# LF_SFF_AC_DC.net
KiCad netlist of a schematic drawn in Altium Designer
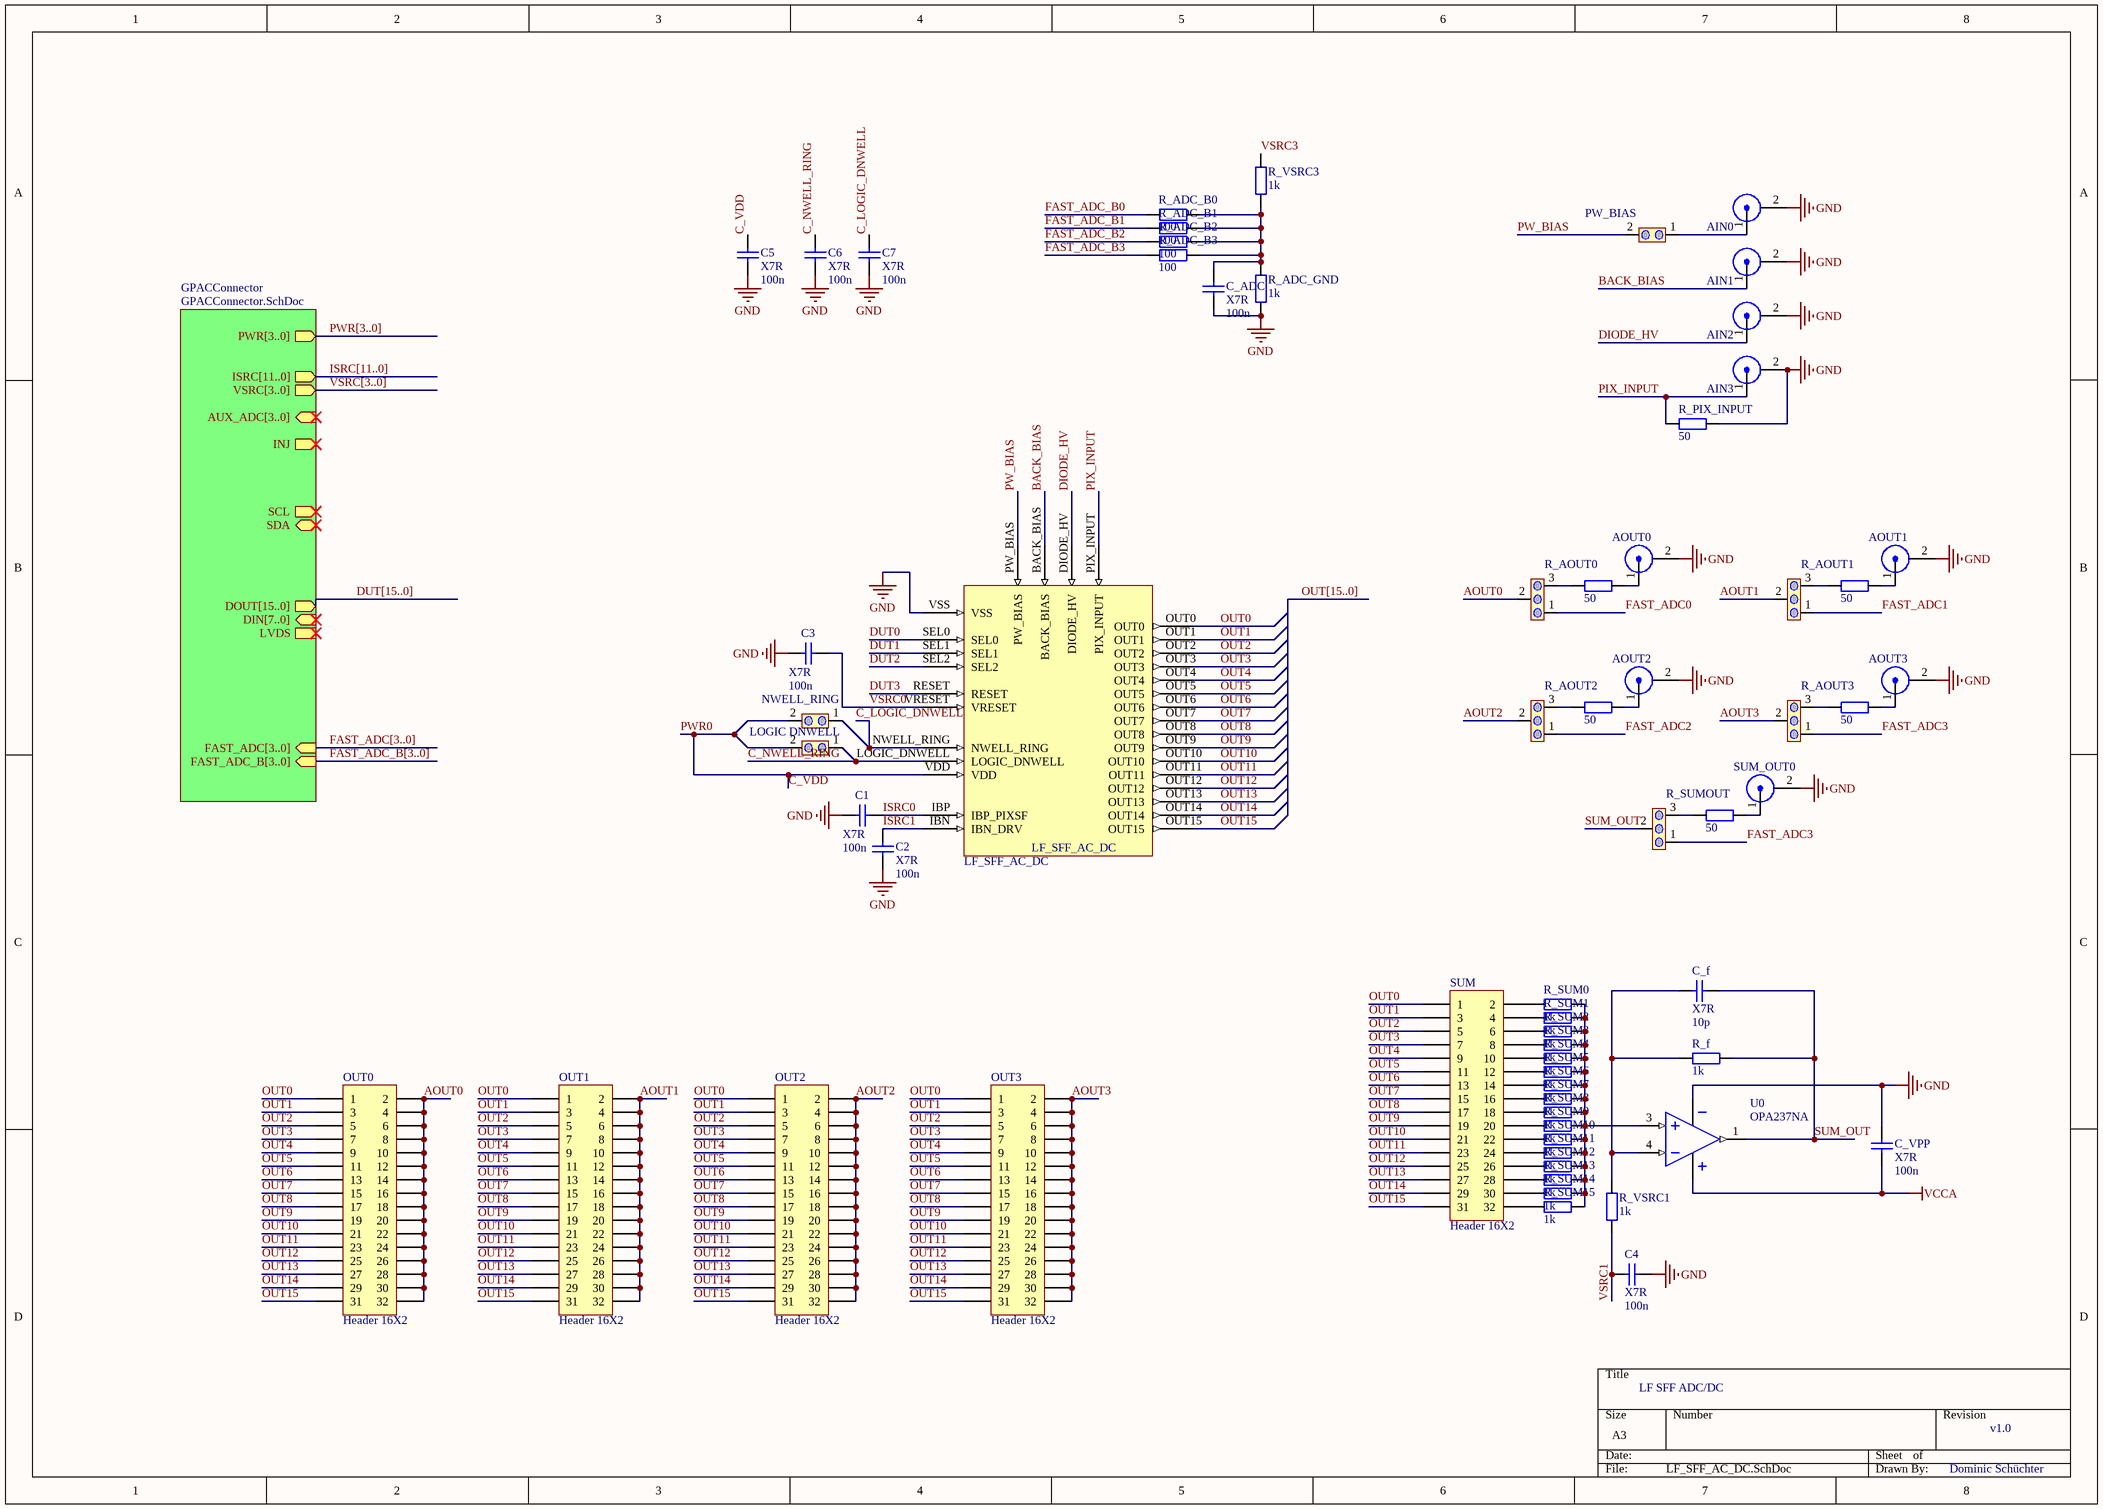
[diagram p0: LF_SFF_AC_DC.SchDoc]

(export (version "E")
  (design (tool "Eeschema 10.0.6"))
  (components
    (comp (ref "AIN0")
      (value "-")
      (footprint "LEMO horiz.")
      (description "LEMO/BNC Buchse, aufrecht od. gewinkelt")
      (fields (field (name "PUBLISHER") "Silab C.H."))
      (libsource (lib "Silab_Lib") (part "LEMO coax"))
    )
    (comp (ref "AIN1")
      (value "-")
      (footprint "LEMO horiz.")
      (description "LEMO/BNC Buchse, aufrecht od. gewinkelt")
      (fields (field (name "PUBLISHER") "Silab C.H."))
      (libsource (lib "Silab_Lib") (part "LEMO coax"))
    )
    (comp (ref "AIN2")
      (value "-")
      (footprint "LEMO horiz.")
      (description "LEMO/BNC Buchse, aufrecht od. gewinkelt")
      (fields (field (name "PUBLISHER") "Silab C.H."))
      (libsource (lib "Silab_Lib") (part "LEMO coax"))
    )
    (comp (ref "AIN3")
      (value "-")
      (footprint "LEMO horiz.")
      (description "LEMO/BNC Buchse, aufrecht od. gewinkelt")
      (fields (field (name "PUBLISHER") "Silab C.H."))
      (libsource (lib "Silab_Lib") (part "LEMO coax"))
    )
    (comp (ref "AOUT0")
      (value "-")
      (footprint "LEMO horiz.")
      (description "LEMO/BNC Buchse, aufrecht od. gewinkelt")
      (fields (field (name "PUBLISHER") "Silab C.H."))
      (libsource (lib "Silab_Lib") (part "LEMO coax"))
    )
    (comp (ref "AOUT1")
      (value "-")
      (footprint "LEMO horiz.")
      (description "LEMO/BNC Buchse, aufrecht od. gewinkelt")
      (fields (field (name "PUBLISHER") "Silab C.H."))
      (libsource (lib "Silab_Lib") (part "LEMO coax"))
    )
    (comp (ref "AOUT2")
      (value "-")
      (footprint "LEMO horiz.")
      (description "LEMO/BNC Buchse, aufrecht od. gewinkelt")
      (fields (field (name "PUBLISHER") "Silab C.H."))
      (libsource (lib "Silab_Lib") (part "LEMO coax"))
    )
    (comp (ref "AOUT3")
      (value "-")
      (footprint "LEMO horiz.")
      (description "LEMO/BNC Buchse, aufrecht od. gewinkelt")
      (fields (field (name "PUBLISHER") "Silab C.H."))
      (libsource (lib "Silab_Lib") (part "LEMO coax"))
    )
    (comp (ref "AOUT_SEL0")
      (value "-")
      (footprint "HDR 1x3")
      (description "Jumper, Solderbridge 1x3")
      (fields (field (name "PUBLISHER") "Silab C.H."))
      (libsource (lib "Silab_Lib") (part "JUMPER 1X3S"))
    )
    (comp (ref "AOUT_SEL1")
      (value "-")
      (footprint "HDR 1x3")
      (description "Jumper, Solderbridge 1x3")
      (fields (field (name "PUBLISHER") "Silab C.H."))
      (libsource (lib "Silab_Lib") (part "JUMPER 1X3S"))
    )
    (comp (ref "AOUT_SEL2")
      (value "-")
      (footprint "HDR 1x3")
      (description "Jumper, Solderbridge 1x3")
      (fields (field (name "PUBLISHER") "Silab C.H."))
      (libsource (lib "Silab_Lib") (part "JUMPER 1X3S"))
    )
    (comp (ref "AOUT_SEL3")
      (value "-")
      (footprint "HDR 1x3")
      (description "Jumper, Solderbridge 1x3")
      (fields (field (name "PUBLISHER") "Silab C.H."))
      (libsource (lib "Silab_Lib") (part "JUMPER 1X3S"))
    )
    (comp (ref "C1")
      (value "X7R")
      (footprint "C0603_imp_N")
      (description "Capacitor")
      (fields (field (name "ALTIUM_VALUE") "100n") (field (name "PUBLISHER") "Silab J.S."))
      (libsource (lib "Silab_Lib") (part "C"))
    )
    (comp (ref "C2")
      (value "X7R")
      (footprint "C0603_imp_N")
      (description "Capacitor")
      (fields (field (name "ALTIUM_VALUE") "100n") (field (name "PUBLISHER") "Silab J.S."))
      (libsource (lib "Silab_Lib") (part "C"))
    )
    (comp (ref "C3")
      (value "X7R")
      (footprint "C0603_imp_N")
      (description "Capacitor")
      (fields (field (name "ALTIUM_VALUE") "100n") (field (name "PUBLISHER") "Silab J.S."))
      (libsource (lib "Silab_Lib") (part "C"))
    )
    (comp (ref "C4")
      (value "X7R")
      (footprint "C0603_imp_N")
      (description "Capacitor")
      (fields (field (name "ALTIUM_VALUE") "100n") (field (name "PUBLISHER") "Silab J.S."))
      (libsource (lib "Silab_Lib") (part "C"))
    )
    (comp (ref "C5")
      (value "X7R")
      (footprint "C0603_imp_N")
      (description "Capacitor")
      (fields (field (name "ALTIUM_VALUE") "100n") (field (name "PUBLISHER") "Silab J.S."))
      (libsource (lib "Silab_Lib") (part "C"))
    )
    (comp (ref "C6")
      (value "X7R")
      (footprint "C0603_imp_N")
      (description "Capacitor")
      (fields (field (name "ALTIUM_VALUE") "100n") (field (name "PUBLISHER") "Silab J.S."))
      (libsource (lib "Silab_Lib") (part "C"))
    )
    (comp (ref "C7")
      (value "X7R")
      (footprint "C0603_imp_N")
      (description "Capacitor")
      (fields (field (name "ALTIUM_VALUE") "100n") (field (name "PUBLISHER") "Silab J.S."))
      (libsource (lib "Silab_Lib") (part "C"))
    )
    (comp (ref "C_ADC")
      (value "X7R")
      (footprint "C0603_imp_N")
      (description "Capacitor")
      (fields (field (name "ALTIUM_VALUE") "100n") (field (name "PUBLISHER") "Silab J.S."))
      (libsource (lib "Silab_Lib") (part "C"))
    )
    (comp (ref "C_f")
      (value "X7R")
      (footprint "C0603_imp_N")
      (description "Capacitor")
      (fields (field (name "ALTIUM_VALUE") "10p") (field (name "PUBLISHER") "Silab J.S."))
      (libsource (lib "Silab_Lib") (part "C"))
    )
    (comp (ref "C_VPP")
      (value "X7R")
      (footprint "C0603_imp_N")
      (description "Capacitor")
      (fields (field (name "ALTIUM_VALUE") "100n") (field (name "PUBLISHER") "Silab J.S."))
      (libsource (lib "Silab_Lib") (part "C"))
    )
    (comp (ref "LF_SFF_AC_DC")
      (value "LF_SFF_AC_DC")
      (footprint "LF_SFF_COMBI")
      (libsource (lib "LF_SFF_AC") (part "LF_SFF_AC"))
    )
    (comp (ref "LOGIC DNWELL")
      (value "-")
      (footprint "CON 1x2 std")
      (description "Jumper, Solderbridge 1x2")
      (fields (field (name "PUBLISHER") "Silab C.H."))
      (libsource (lib "Silab_Lib") (part "JUMPER 1X2S"))
    )
    (comp (ref "NWELL_RING")
      (value "-")
      (footprint "CON 1x2 std")
      (description "Jumper, Solderbridge 1x2")
      (fields (field (name "PUBLISHER") "Silab C.H."))
      (libsource (lib "Silab_Lib") (part "JUMPER 1X2S"))
    )
    (comp (ref "OUT0")
      (value "Header 16X2")
      (footprint "HDR2X16")
      (description "Header, 16-Pin, Dual row")
      (fields (field (name "PUBLISHER") "Altium Limited"))
      (libsource (lib "Miscellaneous Connectors") (part "Header 16X2"))
    )
    (comp (ref "OUT1")
      (value "Header 16X2")
      (footprint "HDR2X16")
      (description "Header, 16-Pin, Dual row")
      (fields (field (name "PUBLISHER") "Altium Limited"))
      (libsource (lib "Miscellaneous Connectors") (part "Header 16X2"))
    )
    (comp (ref "OUT2")
      (value "Header 16X2")
      (footprint "HDR2X16")
      (description "Header, 16-Pin, Dual row")
      (fields (field (name "PUBLISHER") "Altium Limited"))
      (libsource (lib "Miscellaneous Connectors") (part "Header 16X2"))
    )
    (comp (ref "OUT3")
      (value "Header 16X2")
      (footprint "HDR2X16")
      (description "Header, 16-Pin, Dual row")
      (fields (field (name "PUBLISHER") "Altium Limited"))
      (libsource (lib "Miscellaneous Connectors") (part "Header 16X2"))
    )
    (comp (ref "PW_BIAS")
      (value "-")
      (footprint "CON 1x2 std")
      (description "Jumper, Solderbridge 1x2")
      (fields (field (name "PUBLISHER") "Silab C.H."))
      (libsource (lib "Silab_Lib") (part "JUMPER 1X2S"))
    )
    (comp (ref "R_ADC_B0")
      (value "100")
      (footprint "R0603_imp_N")
      (description "SMD Chip Resistor")
      (fields (field (name "Comment") "R") (field (name "PUBLISHER") "Silab J.S."))
      (libsource (lib "Silab_Lib") (part "R"))
    )
    (comp (ref "R_ADC_B1")
      (value "100")
      (footprint "R0603_imp_N")
      (description "SMD Chip Resistor")
      (fields (field (name "Comment") "R") (field (name "PUBLISHER") "Silab J.S."))
      (libsource (lib "Silab_Lib") (part "R"))
    )
    (comp (ref "R_ADC_B2")
      (value "100")
      (footprint "R0603_imp_N")
      (description "SMD Chip Resistor")
      (fields (field (name "Comment") "R") (field (name "PUBLISHER") "Silab J.S."))
      (libsource (lib "Silab_Lib") (part "R"))
    )
    (comp (ref "R_ADC_B3")
      (value "100")
      (footprint "R0603_imp_N")
      (description "SMD Chip Resistor")
      (fields (field (name "Comment") "R") (field (name "PUBLISHER") "Silab J.S."))
      (libsource (lib "Silab_Lib") (part "R"))
    )
    (comp (ref "R_ADC_GND")
      (value "1k")
      (footprint "R0603_imp_N")
      (description "SMD Chip Resistor")
      (fields (field (name "Comment") "R") (field (name "PUBLISHER") "Silab J.S."))
      (libsource (lib "Silab_Lib") (part "R"))
    )
    (comp (ref "R_AOUT0")
      (value "50")
      (footprint "R0603_imp_N")
      (description "SMD Chip Resistor")
      (fields (field (name "Comment") "R") (field (name "PUBLISHER") "Silab J.S."))
      (libsource (lib "Silab_Lib") (part "R"))
    )
    (comp (ref "R_AOUT1")
      (value "50")
      (footprint "R0603_imp_N")
      (description "SMD Chip Resistor")
      (fields (field (name "Comment") "R") (field (name "PUBLISHER") "Silab J.S."))
      (libsource (lib "Silab_Lib") (part "R"))
    )
    (comp (ref "R_AOUT2")
      (value "50")
      (footprint "R0603_imp_N")
      (description "SMD Chip Resistor")
      (fields (field (name "Comment") "R") (field (name "PUBLISHER") "Silab J.S."))
      (libsource (lib "Silab_Lib") (part "R"))
    )
    (comp (ref "R_AOUT3")
      (value "50")
      (footprint "R0603_imp_N")
      (description "SMD Chip Resistor")
      (fields (field (name "Comment") "R") (field (name "PUBLISHER") "Silab J.S."))
      (libsource (lib "Silab_Lib") (part "R"))
    )
    (comp (ref "R_f")
      (value "1k")
      (footprint "R0805_imp_M")
      (description "SMD Chip Resistor")
      (fields (field (name "Comment") "R") (field (name "PUBLISHER") "Silab J.S."))
      (libsource (lib "Silab_Lib") (part "R"))
    )
    (comp (ref "R_PIX_INPUT")
      (value "50")
      (footprint "R0603_imp_N")
      (description "SMD Chip Resistor")
      (fields (field (name "Comment") "R") (field (name "PUBLISHER") "Silab J.S."))
      (libsource (lib "Silab_Lib") (part "R"))
    )
    (comp (ref "R_SUM0")
      (value "1k")
      (footprint "R0805_imp_M")
      (description "SMD Chip Resistor")
      (fields (field (name "Comment") "R") (field (name "PUBLISHER") "Silab J.S."))
      (libsource (lib "Silab_Lib") (part "R"))
    )
    (comp (ref "R_SUM1")
      (value "1k")
      (footprint "R0805_imp_M")
      (description "SMD Chip Resistor")
      (fields (field (name "Comment") "R") (field (name "PUBLISHER") "Silab J.S."))
      (libsource (lib "Silab_Lib") (part "R"))
    )
    (comp (ref "R_SUM2")
      (value "1k")
      (footprint "R0805_imp_M")
      (description "SMD Chip Resistor")
      (fields (field (name "Comment") "R") (field (name "PUBLISHER") "Silab J.S."))
      (libsource (lib "Silab_Lib") (part "R"))
    )
    (comp (ref "R_SUM3")
      (value "1k")
      (footprint "R0805_imp_M")
      (description "SMD Chip Resistor")
      (fields (field (name "Comment") "R") (field (name "PUBLISHER") "Silab J.S."))
      (libsource (lib "Silab_Lib") (part "R"))
    )
    (comp (ref "R_SUM4")
      (value "1k")
      (footprint "R0805_imp_M")
      (description "SMD Chip Resistor")
      (fields (field (name "Comment") "R") (field (name "PUBLISHER") "Silab J.S."))
      (libsource (lib "Silab_Lib") (part "R"))
    )
    (comp (ref "R_SUM5")
      (value "1k")
      (footprint "R0805_imp_M")
      (description "SMD Chip Resistor")
      (fields (field (name "Comment") "R") (field (name "PUBLISHER") "Silab J.S."))
      (libsource (lib "Silab_Lib") (part "R"))
    )
    (comp (ref "R_SUM6")
      (value "1k")
      (footprint "R0805_imp_M")
      (description "SMD Chip Resistor")
      (fields (field (name "Comment") "R") (field (name "PUBLISHER") "Silab J.S."))
      (libsource (lib "Silab_Lib") (part "R"))
    )
    (comp (ref "R_SUM7")
      (value "1k")
      (footprint "R0805_imp_M")
      (description "SMD Chip Resistor")
      (fields (field (name "Comment") "R") (field (name "PUBLISHER") "Silab J.S."))
      (libsource (lib "Silab_Lib") (part "R"))
    )
    (comp (ref "R_SUM8")
      (value "1k")
      (footprint "R0805_imp_M")
      (description "SMD Chip Resistor")
      (fields (field (name "Comment") "R") (field (name "PUBLISHER") "Silab J.S."))
      (libsource (lib "Silab_Lib") (part "R"))
    )
    (comp (ref "R_SUM9")
      (value "1k")
      (footprint "R0805_imp_M")
      (description "SMD Chip Resistor")
      (fields (field (name "Comment") "R") (field (name "PUBLISHER") "Silab J.S."))
      (libsource (lib "Silab_Lib") (part "R"))
    )
    (comp (ref "R_SUM10")
      (value "1k")
      (footprint "R0805_imp_M")
      (description "SMD Chip Resistor")
      (fields (field (name "Comment") "R") (field (name "PUBLISHER") "Silab J.S."))
      (libsource (lib "Silab_Lib") (part "R"))
    )
    (comp (ref "R_SUM11")
      (value "1k")
      (footprint "R0805_imp_M")
      (description "SMD Chip Resistor")
      (fields (field (name "Comment") "R") (field (name "PUBLISHER") "Silab J.S."))
      (libsource (lib "Silab_Lib") (part "R"))
    )
    (comp (ref "R_SUM12")
      (value "1k")
      (footprint "R0805_imp_M")
      (description "SMD Chip Resistor")
      (fields (field (name "Comment") "R") (field (name "PUBLISHER") "Silab J.S."))
      (libsource (lib "Silab_Lib") (part "R"))
    )
    (comp (ref "R_SUM13")
      (value "1k")
      (footprint "R0805_imp_M")
      (description "SMD Chip Resistor")
      (fields (field (name "Comment") "R") (field (name "PUBLISHER") "Silab J.S."))
      (libsource (lib "Silab_Lib") (part "R"))
    )
    (comp (ref "R_SUM14")
      (value "1k")
      (footprint "R0805_imp_M")
      (description "SMD Chip Resistor")
      (fields (field (name "Comment") "R") (field (name "PUBLISHER") "Silab J.S."))
      (libsource (lib "Silab_Lib") (part "R"))
    )
    (comp (ref "R_SUM15")
      (value "1k")
      (footprint "R0805_imp_M")
      (description "SMD Chip Resistor")
      (fields (field (name "Comment") "R") (field (name "PUBLISHER") "Silab J.S."))
      (libsource (lib "Silab_Lib") (part "R"))
    )
    (comp (ref "R_SUMOUT")
      (value "50")
      (footprint "R0603_imp_N")
      (description "SMD Chip Resistor")
      (fields (field (name "Comment") "R") (field (name "PUBLISHER") "Silab J.S."))
      (libsource (lib "Silab_Lib") (part "R"))
    )
    (comp (ref "R_VSRC1")
      (value "1k")
      (footprint "R0805_imp_M")
      (description "SMD Chip Resistor")
      (fields (field (name "Comment") "R") (field (name "PUBLISHER") "Silab J.S."))
      (libsource (lib "Silab_Lib") (part "R"))
    )
    (comp (ref "R_VSRC3")
      (value "1k")
      (footprint "R0603_imp_N")
      (description "SMD Chip Resistor")
      (fields (field (name "Comment") "R") (field (name "PUBLISHER") "Silab J.S."))
      (libsource (lib "Silab_Lib") (part "R"))
    )
    (comp (ref "SUM")
      (value "Header 16X2")
      (footprint "HDR2X16")
      (description "Header, 16-Pin, Dual row")
      (fields (field (name "PUBLISHER") "Altium Limited"))
      (libsource (lib "Miscellaneous Connectors") (part "Header 16X2"))
    )
    (comp (ref "SUM_OUT0")
      (value "-")
      (footprint "LEMO horiz.")
      (description "LEMO/BNC Buchse, aufrecht od. gewinkelt")
      (fields (field (name "PUBLISHER") "Silab C.H."))
      (libsource (lib "Silab_Lib") (part "LEMO coax"))
    )
    (comp (ref "SUM_SELECT")
      (value "-")
      (footprint "HDR 1x3")
      (description "Jumper, Solderbridge 1x3")
      (fields (field (name "PUBLISHER") "Silab C.H."))
      (libsource (lib "Silab_Lib") (part "JUMPER 1X3S"))
    )
    (comp (ref "U0")
      (value "OPA237")
      (footprint "SOT23-5")
      (description "OpAmp (TI), single supply up to +36V;")
      (fields (field (name "TYPE_1") "OPA237NA") (field (name "PUBLISHER") "Silab J.S."))
      (libsource (lib "Silab_Lib") (part "OPA237"))
    )
  )
  (nets
    (net (code "27") (name "/AOUT0") (class "Default")
      (node (ref "AOUT_SEL0") (pin "2") (pinfunction "2_2") (pintype "passive"))
      (node (ref "OUT0") (pin "10") (pinfunction "10_10") (pintype "passive"))
      (node (ref "OUT0") (pin "12") (pinfunction "12_12") (pintype "passive"))
      (node (ref "OUT0") (pin "14") (pinfunction "14_14") (pintype "passive"))
      (node (ref "OUT0") (pin "16") (pinfunction "16_16") (pintype "passive"))
      (node (ref "OUT0") (pin "18") (pinfunction "18_18") (pintype "passive"))
      (node (ref "OUT0") (pin "2") (pinfunction "2_2") (pintype "passive"))
      (node (ref "OUT0") (pin "20") (pinfunction "20_20") (pintype "passive"))
      (node (ref "OUT0") (pin "22") (pinfunction "22_22") (pintype "passive"))
      (node (ref "OUT0") (pin "24") (pinfunction "24_24") (pintype "passive"))
      (node (ref "OUT0") (pin "26") (pinfunction "26_26") (pintype "passive"))
      (node (ref "OUT0") (pin "28") (pinfunction "28_28") (pintype "passive"))
      (node (ref "OUT0") (pin "30") (pinfunction "30_30") (pintype "passive"))
      (node (ref "OUT0") (pin "32") (pinfunction "32_32") (pintype "passive"))
      (node (ref "OUT0") (pin "4") (pinfunction "4_4") (pintype "passive"))
      (node (ref "OUT0") (pin "6") (pinfunction "6_6") (pintype "passive"))
      (node (ref "OUT0") (pin "8") (pinfunction "8_8") (pintype "passive"))
    )
    (net (code "28") (name "/AOUT1") (class "Default")
      (node (ref "AOUT_SEL1") (pin "2") (pinfunction "2_2") (pintype "passive"))
      (node (ref "OUT1") (pin "10") (pinfunction "10_10") (pintype "passive"))
      (node (ref "OUT1") (pin "12") (pinfunction "12_12") (pintype "passive"))
      (node (ref "OUT1") (pin "14") (pinfunction "14_14") (pintype "passive"))
      (node (ref "OUT1") (pin "16") (pinfunction "16_16") (pintype "passive"))
      (node (ref "OUT1") (pin "18") (pinfunction "18_18") (pintype "passive"))
      (node (ref "OUT1") (pin "2") (pinfunction "2_2") (pintype "passive"))
      (node (ref "OUT1") (pin "20") (pinfunction "20_20") (pintype "passive"))
      (node (ref "OUT1") (pin "22") (pinfunction "22_22") (pintype "passive"))
      (node (ref "OUT1") (pin "24") (pinfunction "24_24") (pintype "passive"))
      (node (ref "OUT1") (pin "26") (pinfunction "26_26") (pintype "passive"))
      (node (ref "OUT1") (pin "28") (pinfunction "28_28") (pintype "passive"))
      (node (ref "OUT1") (pin "30") (pinfunction "30_30") (pintype "passive"))
      (node (ref "OUT1") (pin "32") (pinfunction "32_32") (pintype "passive"))
      (node (ref "OUT1") (pin "4") (pinfunction "4_4") (pintype "passive"))
      (node (ref "OUT1") (pin "6") (pinfunction "6_6") (pintype "passive"))
      (node (ref "OUT1") (pin "8") (pinfunction "8_8") (pintype "passive"))
    )
    (net (code "29") (name "/AOUT2") (class "Default")
      (node (ref "AOUT_SEL2") (pin "2") (pinfunction "2_2") (pintype "passive"))
      (node (ref "OUT2") (pin "10") (pinfunction "10_10") (pintype "passive"))
      (node (ref "OUT2") (pin "12") (pinfunction "12_12") (pintype "passive"))
      (node (ref "OUT2") (pin "14") (pinfunction "14_14") (pintype "passive"))
      (node (ref "OUT2") (pin "16") (pinfunction "16_16") (pintype "passive"))
      (node (ref "OUT2") (pin "18") (pinfunction "18_18") (pintype "passive"))
      (node (ref "OUT2") (pin "2") (pinfunction "2_2") (pintype "passive"))
      (node (ref "OUT2") (pin "20") (pinfunction "20_20") (pintype "passive"))
      (node (ref "OUT2") (pin "22") (pinfunction "22_22") (pintype "passive"))
      (node (ref "OUT2") (pin "24") (pinfunction "24_24") (pintype "passive"))
      (node (ref "OUT2") (pin "26") (pinfunction "26_26") (pintype "passive"))
      (node (ref "OUT2") (pin "28") (pinfunction "28_28") (pintype "passive"))
      (node (ref "OUT2") (pin "30") (pinfunction "30_30") (pintype "passive"))
      (node (ref "OUT2") (pin "32") (pinfunction "32_32") (pintype "passive"))
      (node (ref "OUT2") (pin "4") (pinfunction "4_4") (pintype "passive"))
      (node (ref "OUT2") (pin "6") (pinfunction "6_6") (pintype "passive"))
      (node (ref "OUT2") (pin "8") (pinfunction "8_8") (pintype "passive"))
    )
    (net (code "30") (name "/AOUT3") (class "Default")
      (node (ref "AOUT_SEL3") (pin "2") (pinfunction "2_2") (pintype "passive"))
      (node (ref "OUT3") (pin "10") (pinfunction "10_10") (pintype "passive"))
      (node (ref "OUT3") (pin "12") (pinfunction "12_12") (pintype "passive"))
      (node (ref "OUT3") (pin "14") (pinfunction "14_14") (pintype "passive"))
      (node (ref "OUT3") (pin "16") (pinfunction "16_16") (pintype "passive"))
      (node (ref "OUT3") (pin "18") (pinfunction "18_18") (pintype "passive"))
      (node (ref "OUT3") (pin "2") (pinfunction "2_2") (pintype "passive"))
      (node (ref "OUT3") (pin "20") (pinfunction "20_20") (pintype "passive"))
      (node (ref "OUT3") (pin "22") (pinfunction "22_22") (pintype "passive"))
      (node (ref "OUT3") (pin "24") (pinfunction "24_24") (pintype "passive"))
      (node (ref "OUT3") (pin "26") (pinfunction "26_26") (pintype "passive"))
      (node (ref "OUT3") (pin "28") (pinfunction "28_28") (pintype "passive"))
      (node (ref "OUT3") (pin "30") (pinfunction "30_30") (pintype "passive"))
      (node (ref "OUT3") (pin "32") (pinfunction "32_32") (pintype "passive"))
      (node (ref "OUT3") (pin "4") (pinfunction "4_4") (pintype "passive"))
      (node (ref "OUT3") (pin "6") (pinfunction "6_6") (pintype "passive"))
      (node (ref "OUT3") (pin "8") (pinfunction "8_8") (pintype "passive"))
    )
    (net (code "32") (name "/BACK_BIAS") (class "Default")
      (node (ref "AIN1") (pin "1") (pinfunction "1_1") (pintype "passive"))
      (node (ref "LF_SFF_AC_DC") (pin "BACK_BIAS") (pinfunction "BACK_BIAS_BACK_BIAS") (pintype "input"))
    )
    (net (code "33") (name "/C_LOGIC_DNWELL") (class "Default")
      (node (ref "C7") (pin "1") (pinfunction "1_1") (pintype "passive"))
      (node (ref "LF_SFF_AC_DC") (pin "NWELL_RING") (pinfunction "NWELL_RING_NWELL_RING") (pintype "input"))
      (node (ref "NWELL_RING") (pin "1") (pinfunction "1_1") (pintype "passive"))
    )
    (net (code "34") (name "/C_NWELL_RING") (class "Default")
      (node (ref "C6") (pin "1") (pinfunction "1_1") (pintype "passive"))
      (node (ref "LF_SFF_AC_DC") (pin "LOGIC_DNWELL") (pinfunction "LOGIC_DNWELL_LOGIC_DNWELL") (pintype "input"))
      (node (ref "LOGIC DNWELL") (pin "1") (pinfunction "1_1") (pintype "passive"))
    )
    (net (code "36") (name "/DIODE_HV") (class "Default")
      (node (ref "AIN2") (pin "1") (pinfunction "1_1") (pintype "passive"))
      (node (ref "LF_SFF_AC_DC") (pin "DIODE_HV") (pinfunction "DIODE_HV_DIODE_HV") (pintype "input"))
    )
    (net (code "37") (name "/DUT0") (class "Default")
      (node (ref "LF_SFF_AC_DC") (pin "SEL0") (pinfunction "SEL0_SEL0") (pintype "input"))
    )
    (net (code "38") (name "/DUT1") (class "Default")
      (node (ref "LF_SFF_AC_DC") (pin "SEL1") (pinfunction "SEL1_SEL1") (pintype "input"))
    )
    (net (code "39") (name "/DUT2") (class "Default")
      (node (ref "LF_SFF_AC_DC") (pin "SEL2") (pinfunction "SEL2_SEL2") (pintype "input"))
    )
    (net (code "40") (name "/DUT3") (class "Default")
      (node (ref "LF_SFF_AC_DC") (pin "RESET") (pinfunction "RESET_RESET") (pintype "input"))
    )
    (net (code "42") (name "/FAST_ADC0") (class "Default")
      (node (ref "AOUT_SEL0") (pin "1") (pinfunction "1_1") (pintype "passive"))
    )
    (net (code "43") (name "/FAST_ADC1") (class "Default")
      (node (ref "AOUT_SEL1") (pin "1") (pinfunction "1_1") (pintype "passive"))
    )
    (net (code "44") (name "/FAST_ADC2") (class "Default")
      (node (ref "AOUT_SEL2") (pin "1") (pinfunction "1_1") (pintype "passive"))
    )
    (net (code "45") (name "/FAST_ADC3") (class "Default")
      (node (ref "AOUT_SEL3") (pin "1") (pinfunction "1_1") (pintype "passive"))
      (node (ref "SUM_SELECT") (pin "1") (pinfunction "1_1") (pintype "passive"))
    )
    (net (code "47") (name "/FAST_ADC_B0") (class "Default")
      (node (ref "R_ADC_B0") (pin "1") (pinfunction "1_1") (pintype "passive"))
    )
    (net (code "48") (name "/FAST_ADC_B1") (class "Default")
      (node (ref "R_ADC_B1") (pin "1") (pinfunction "1_1") (pintype "passive"))
    )
    (net (code "49") (name "/FAST_ADC_B2") (class "Default")
      (node (ref "R_ADC_B2") (pin "1") (pinfunction "1_1") (pintype "passive"))
    )
    (net (code "50") (name "/FAST_ADC_B3") (class "Default")
      (node (ref "R_ADC_B3") (pin "1") (pinfunction "1_1") (pintype "passive"))
    )
    (net (code "53") (name "/ISRC0") (class "Default")
      (node (ref "C1") (pin "1") (pinfunction "1_1") (pintype "passive"))
      (node (ref "LF_SFF_AC_DC") (pin "IBP") (pinfunction "IBP_PIXSF_IBP") (pintype "input"))
    )
    (net (code "54") (name "/ISRC1") (class "Default")
      (node (ref "C2") (pin "1") (pinfunction "1_1") (pintype "passive"))
      (node (ref "LF_SFF_AC_DC") (pin "IBN") (pinfunction "IBN_DRV_IBN") (pintype "input"))
    )
    (net (code "57") (name "/OUT0") (class "Default")
      (node (ref "LF_SFF_AC_DC") (pin "OUT0") (pinfunction "OUT0_OUT0") (pintype "output"))
      (node (ref "OUT0") (pin "1") (pinfunction "1_1") (pintype "passive"))
      (node (ref "OUT1") (pin "1") (pinfunction "1_1") (pintype "passive"))
      (node (ref "OUT2") (pin "1") (pinfunction "1_1") (pintype "passive"))
      (node (ref "OUT3") (pin "1") (pinfunction "1_1") (pintype "passive"))
      (node (ref "SUM") (pin "1") (pinfunction "1_1") (pintype "passive"))
    )
    (net (code "58") (name "/OUT1") (class "Default")
      (node (ref "LF_SFF_AC_DC") (pin "OUT1") (pinfunction "OUT1_OUT1") (pintype "output"))
      (node (ref "OUT0") (pin "3") (pinfunction "3_3") (pintype "passive"))
      (node (ref "OUT1") (pin "3") (pinfunction "3_3") (pintype "passive"))
      (node (ref "OUT2") (pin "3") (pinfunction "3_3") (pintype "passive"))
      (node (ref "OUT3") (pin "3") (pinfunction "3_3") (pintype "passive"))
      (node (ref "SUM") (pin "3") (pinfunction "3_3") (pintype "passive"))
    )
    (net (code "59") (name "/OUT2") (class "Default")
      (node (ref "LF_SFF_AC_DC") (pin "OUT2") (pinfunction "OUT2_OUT2") (pintype "output"))
      (node (ref "OUT0") (pin "5") (pinfunction "5_5") (pintype "passive"))
      (node (ref "OUT1") (pin "5") (pinfunction "5_5") (pintype "passive"))
      (node (ref "OUT2") (pin "5") (pinfunction "5_5") (pintype "passive"))
      (node (ref "OUT3") (pin "5") (pinfunction "5_5") (pintype "passive"))
      (node (ref "SUM") (pin "5") (pinfunction "5_5") (pintype "passive"))
    )
    (net (code "60") (name "/OUT3") (class "Default")
      (node (ref "LF_SFF_AC_DC") (pin "OUT3") (pinfunction "OUT3_OUT3") (pintype "output"))
      (node (ref "OUT0") (pin "7") (pinfunction "7_7") (pintype "passive"))
      (node (ref "OUT1") (pin "7") (pinfunction "7_7") (pintype "passive"))
      (node (ref "OUT2") (pin "7") (pinfunction "7_7") (pintype "passive"))
      (node (ref "OUT3") (pin "7") (pinfunction "7_7") (pintype "passive"))
      (node (ref "SUM") (pin "7") (pinfunction "7_7") (pintype "passive"))
    )
    (net (code "61") (name "/OUT4") (class "Default")
      (node (ref "LF_SFF_AC_DC") (pin "OUT4") (pinfunction "OUT4_OUT4") (pintype "output"))
      (node (ref "OUT0") (pin "9") (pinfunction "9_9") (pintype "passive"))
      (node (ref "OUT1") (pin "9") (pinfunction "9_9") (pintype "passive"))
      (node (ref "OUT2") (pin "9") (pinfunction "9_9") (pintype "passive"))
      (node (ref "OUT3") (pin "9") (pinfunction "9_9") (pintype "passive"))
      (node (ref "SUM") (pin "9") (pinfunction "9_9") (pintype "passive"))
    )
    (net (code "62") (name "/OUT5") (class "Default")
      (node (ref "LF_SFF_AC_DC") (pin "OUT5") (pinfunction "OUT5_OUT5") (pintype "output"))
      (node (ref "OUT0") (pin "11") (pinfunction "11_11") (pintype "passive"))
      (node (ref "OUT1") (pin "11") (pinfunction "11_11") (pintype "passive"))
      (node (ref "OUT2") (pin "11") (pinfunction "11_11") (pintype "passive"))
      (node (ref "OUT3") (pin "11") (pinfunction "11_11") (pintype "passive"))
      (node (ref "SUM") (pin "11") (pinfunction "11_11") (pintype "passive"))
    )
    (net (code "63") (name "/OUT6") (class "Default")
      (node (ref "LF_SFF_AC_DC") (pin "OUT6") (pinfunction "OUT6_OUT6") (pintype "output"))
      (node (ref "OUT0") (pin "13") (pinfunction "13_13") (pintype "passive"))
      (node (ref "OUT1") (pin "13") (pinfunction "13_13") (pintype "passive"))
      (node (ref "OUT2") (pin "13") (pinfunction "13_13") (pintype "passive"))
      (node (ref "OUT3") (pin "13") (pinfunction "13_13") (pintype "passive"))
      (node (ref "SUM") (pin "13") (pinfunction "13_13") (pintype "passive"))
    )
    (net (code "64") (name "/OUT7") (class "Default")
      (node (ref "LF_SFF_AC_DC") (pin "OUT7") (pinfunction "OUT7_OUT7") (pintype "output"))
      (node (ref "OUT0") (pin "15") (pinfunction "15_15") (pintype "passive"))
      (node (ref "OUT1") (pin "15") (pinfunction "15_15") (pintype "passive"))
      (node (ref "OUT2") (pin "15") (pinfunction "15_15") (pintype "passive"))
      (node (ref "OUT3") (pin "15") (pinfunction "15_15") (pintype "passive"))
      (node (ref "SUM") (pin "15") (pinfunction "15_15") (pintype "passive"))
    )
    (net (code "65") (name "/OUT8") (class "Default")
      (node (ref "LF_SFF_AC_DC") (pin "OUT8") (pinfunction "OUT8_OUT8") (pintype "output"))
      (node (ref "OUT0") (pin "17") (pinfunction "17_17") (pintype "passive"))
      (node (ref "OUT1") (pin "17") (pinfunction "17_17") (pintype "passive"))
      (node (ref "OUT2") (pin "17") (pinfunction "17_17") (pintype "passive"))
      (node (ref "OUT3") (pin "17") (pinfunction "17_17") (pintype "passive"))
      (node (ref "SUM") (pin "17") (pinfunction "17_17") (pintype "passive"))
    )
    (net (code "66") (name "/OUT9") (class "Default")
      (node (ref "LF_SFF_AC_DC") (pin "OUT9") (pinfunction "OUT9_OUT9") (pintype "output"))
      (node (ref "OUT0") (pin "19") (pinfunction "19_19") (pintype "passive"))
      (node (ref "OUT1") (pin "19") (pinfunction "19_19") (pintype "passive"))
      (node (ref "OUT2") (pin "19") (pinfunction "19_19") (pintype "passive"))
      (node (ref "OUT3") (pin "19") (pinfunction "19_19") (pintype "passive"))
      (node (ref "SUM") (pin "19") (pinfunction "19_19") (pintype "passive"))
    )
    (net (code "67") (name "/OUT10") (class "Default")
      (node (ref "LF_SFF_AC_DC") (pin "OUT10") (pinfunction "OUT10_OUT10") (pintype "output"))
      (node (ref "OUT0") (pin "21") (pinfunction "21_21") (pintype "passive"))
      (node (ref "OUT1") (pin "21") (pinfunction "21_21") (pintype "passive"))
      (node (ref "OUT2") (pin "21") (pinfunction "21_21") (pintype "passive"))
      (node (ref "OUT3") (pin "21") (pinfunction "21_21") (pintype "passive"))
      (node (ref "SUM") (pin "21") (pinfunction "21_21") (pintype "passive"))
    )
    (net (code "68") (name "/OUT11") (class "Default")
      (node (ref "LF_SFF_AC_DC") (pin "OUT11") (pinfunction "OUT11_OUT11") (pintype "output"))
      (node (ref "OUT0") (pin "23") (pinfunction "23_23") (pintype "passive"))
      (node (ref "OUT1") (pin "23") (pinfunction "23_23") (pintype "passive"))
      (node (ref "OUT2") (pin "23") (pinfunction "23_23") (pintype "passive"))
      (node (ref "OUT3") (pin "23") (pinfunction "23_23") (pintype "passive"))
      (node (ref "SUM") (pin "23") (pinfunction "23_23") (pintype "passive"))
    )
    (net (code "69") (name "/OUT12") (class "Default")
      (node (ref "LF_SFF_AC_DC") (pin "OUT12") (pinfunction "OUT12_OUT12") (pintype "output"))
      (node (ref "OUT0") (pin "25") (pinfunction "25_25") (pintype "passive"))
      (node (ref "OUT1") (pin "25") (pinfunction "25_25") (pintype "passive"))
      (node (ref "OUT2") (pin "25") (pinfunction "25_25") (pintype "passive"))
      (node (ref "OUT3") (pin "25") (pinfunction "25_25") (pintype "passive"))
      (node (ref "SUM") (pin "25") (pinfunction "25_25") (pintype "passive"))
    )
    (net (code "70") (name "/OUT13") (class "Default")
      (node (ref "LF_SFF_AC_DC") (pin "OUT13") (pinfunction "OUT13_OUT13") (pintype "output"))
      (node (ref "OUT0") (pin "27") (pinfunction "27_27") (pintype "passive"))
      (node (ref "OUT1") (pin "27") (pinfunction "27_27") (pintype "passive"))
      (node (ref "OUT2") (pin "27") (pinfunction "27_27") (pintype "passive"))
      (node (ref "OUT3") (pin "27") (pinfunction "27_27") (pintype "passive"))
      (node (ref "SUM") (pin "27") (pinfunction "27_27") (pintype "passive"))
    )
    (net (code "71") (name "/OUT14") (class "Default")
      (node (ref "LF_SFF_AC_DC") (pin "OUT14") (pinfunction "OUT14_OUT14") (pintype "output"))
      (node (ref "OUT0") (pin "29") (pinfunction "29_29") (pintype "passive"))
      (node (ref "OUT1") (pin "29") (pinfunction "29_29") (pintype "passive"))
      (node (ref "OUT2") (pin "29") (pinfunction "29_29") (pintype "passive"))
      (node (ref "OUT3") (pin "29") (pinfunction "29_29") (pintype "passive"))
      (node (ref "SUM") (pin "29") (pinfunction "29_29") (pintype "passive"))
    )
    (net (code "72") (name "/OUT15") (class "Default")
      (node (ref "LF_SFF_AC_DC") (pin "OUT15") (pinfunction "OUT15_OUT15") (pintype "output"))
      (node (ref "OUT0") (pin "31") (pinfunction "31_31") (pintype "passive"))
      (node (ref "OUT1") (pin "31") (pinfunction "31_31") (pintype "passive"))
      (node (ref "OUT2") (pin "31") (pinfunction "31_31") (pintype "passive"))
      (node (ref "OUT3") (pin "31") (pinfunction "31_31") (pintype "passive"))
      (node (ref "SUM") (pin "31") (pinfunction "31_31") (pintype "passive"))
    )
    (net (code "74") (name "/PIX_INPUT") (class "Default")
      (node (ref "AIN3") (pin "1") (pinfunction "1_1") (pintype "passive"))
      (node (ref "LF_SFF_AC_DC") (pin "PIX_INPUT") (pinfunction "PIX_INPUT_PIX_INPUT") (pintype "input"))
      (node (ref "R_PIX_INPUT") (pin "1") (pinfunction "1_1") (pintype "passive"))
    )
    (net (code "75") (name "/PWR0") (class "Default")
      (node (ref "C5") (pin "1") (pinfunction "1_1") (pintype "passive"))
      (node (ref "LF_SFF_AC_DC") (pin "VDD") (pinfunction "VDD_VDD") (pintype "input"))
      (node (ref "LOGIC DNWELL") (pin "2") (pinfunction "2_2") (pintype "passive"))
      (node (ref "NWELL_RING") (pin "2") (pinfunction "2_2") (pintype "passive"))
    )
    (net (code "77") (name "/PW_BIAS") (class "Default")
      (node (ref "LF_SFF_AC_DC") (pin "PW_BIAS") (pinfunction "PW_BIAS_PW_BIAS") (pintype "input"))
      (node (ref "PW_BIAS") (pin "2") (pinfunction "2_2") (pintype "passive"))
    )
    (net (code "80") (name "/SUM_OUT") (class "Default")
      (node (ref "C_f") (pin "2") (pinfunction "2_2") (pintype "passive"))
      (node (ref "R_f") (pin "2") (pinfunction "2_2") (pintype "passive"))
      (node (ref "SUM_SELECT") (pin "2") (pinfunction "2_2") (pintype "passive"))
      (node (ref "U0") (pin "1") (pinfunction "OUT_1") (pintype "output"))
    )
    (net (code "81") (name "/VSRC0") (class "Default")
      (node (ref "C3") (pin "1") (pinfunction "1_1") (pintype "passive"))
      (node (ref "LF_SFF_AC_DC") (pin "VRESET") (pinfunction "VRESET_VRESET") (pintype "input"))
    )
    (net (code "82") (name "/VSRC1") (class "Default")
      (node (ref "C4") (pin "1") (pinfunction "1_1") (pintype "passive"))
      (node (ref "R_VSRC1") (pin "2") (pinfunction "2_2") (pintype "passive"))
    )
    (net (code "83") (name "/VSRC3") (class "Default")
      (node (ref "R_VSRC3") (pin "2") (pinfunction "2_2") (pintype "passive"))
    )
    (net (code "85") (name "GND") (class "Default")
      (node (ref "AIN0") (pin "2") (pinfunction "2_2") (pintype "passive"))
      (node (ref "AIN1") (pin "2") (pinfunction "2_2") (pintype "passive"))
      (node (ref "AIN2") (pin "2") (pinfunction "2_2") (pintype "passive"))
      (node (ref "AIN3") (pin "2") (pinfunction "2_2") (pintype "passive"))
      (node (ref "AOUT0") (pin "2") (pinfunction "2_2") (pintype "passive"))
      (node (ref "AOUT1") (pin "2") (pinfunction "2_2") (pintype "passive"))
      (node (ref "AOUT2") (pin "2") (pinfunction "2_2") (pintype "passive"))
      (node (ref "AOUT3") (pin "2") (pinfunction "2_2") (pintype "passive"))
      (node (ref "C1") (pin "2") (pinfunction "2_2") (pintype "passive"))
      (node (ref "C2") (pin "2") (pinfunction "2_2") (pintype "passive"))
      (node (ref "C3") (pin "2") (pinfunction "2_2") (pintype "passive"))
      (node (ref "C4") (pin "2") (pinfunction "2_2") (pintype "passive"))
      (node (ref "C5") (pin "2") (pinfunction "2_2") (pintype "passive"))
      (node (ref "C6") (pin "2") (pinfunction "2_2") (pintype "passive"))
      (node (ref "C7") (pin "2") (pinfunction "2_2") (pintype "passive"))
      (node (ref "C_ADC") (pin "1") (pinfunction "1_1") (pintype "passive"))
      (node (ref "C_VPP") (pin "1") (pinfunction "1_1") (pintype "passive"))
      (node (ref "LF_SFF_AC_DC") (pin "VSS") (pinfunction "VSS_VSS") (pintype "input"))
      (node (ref "R_ADC_GND") (pin "1") (pinfunction "1_1") (pintype "passive"))
      (node (ref "R_PIX_INPUT") (pin "2") (pinfunction "2_2") (pintype "passive"))
      (node (ref "SUM_OUT0") (pin "2") (pinfunction "2_2") (pintype "passive"))
      (node (ref "U0") (pin "2") (pinfunction "V-_2") (pintype "power_in"))
    )
    (net (code "86") (name "Net-(AIN0-Pad1)") (class "Default")
      (node (ref "AIN0") (pin "1") (pinfunction "1_1") (pintype "passive"))
      (node (ref "PW_BIAS") (pin "1") (pinfunction "1_1") (pintype "passive"))
    )
    (net (code "87") (name "Net-(AOUT0-Pad1)") (class "Default")
      (node (ref "AOUT0") (pin "1") (pinfunction "1_1") (pintype "passive"))
      (node (ref "R_AOUT0") (pin "1") (pinfunction "1_1") (pintype "passive"))
    )
    (net (code "88") (name "Net-(AOUT1-Pad1)") (class "Default")
      (node (ref "AOUT1") (pin "1") (pinfunction "1_1") (pintype "passive"))
      (node (ref "R_AOUT1") (pin "1") (pinfunction "1_1") (pintype "passive"))
    )
    (net (code "89") (name "Net-(AOUT2-Pad1)") (class "Default")
      (node (ref "AOUT2") (pin "1") (pinfunction "1_1") (pintype "passive"))
      (node (ref "R_AOUT2") (pin "1") (pinfunction "1_1") (pintype "passive"))
    )
    (net (code "90") (name "Net-(AOUT3-Pad1)") (class "Default")
      (node (ref "AOUT3") (pin "1") (pinfunction "1_1") (pintype "passive"))
      (node (ref "R_AOUT3") (pin "1") (pinfunction "1_1") (pintype "passive"))
    )
    (net (code "91") (name "Net-(AOUT_SEL0-Pad3)") (class "Default")
      (node (ref "AOUT_SEL0") (pin "3") (pinfunction "3_3") (pintype "passive"))
      (node (ref "R_AOUT0") (pin "2") (pinfunction "2_2") (pintype "passive"))
    )
    (net (code "92") (name "Net-(AOUT_SEL1-Pad3)") (class "Default")
      (node (ref "AOUT_SEL1") (pin "3") (pinfunction "3_3") (pintype "passive"))
      (node (ref "R_AOUT1") (pin "2") (pinfunction "2_2") (pintype "passive"))
    )
    (net (code "93") (name "Net-(AOUT_SEL2-Pad3)") (class "Default")
      (node (ref "AOUT_SEL2") (pin "3") (pinfunction "3_3") (pintype "passive"))
      (node (ref "R_AOUT2") (pin "2") (pinfunction "2_2") (pintype "passive"))
    )
    (net (code "94") (name "Net-(AOUT_SEL3-Pad3)") (class "Default")
      (node (ref "AOUT_SEL3") (pin "3") (pinfunction "3_3") (pintype "passive"))
      (node (ref "R_AOUT3") (pin "2") (pinfunction "2_2") (pintype "passive"))
    )
    (net (code "95") (name "Net-(C_ADC-Pad2)") (class "Default")
      (node (ref "C_ADC") (pin "2") (pinfunction "2_2") (pintype "passive"))
      (node (ref "R_ADC_B0") (pin "2") (pinfunction "2_2") (pintype "passive"))
      (node (ref "R_ADC_B1") (pin "2") (pinfunction "2_2") (pintype "passive"))
      (node (ref "R_ADC_B2") (pin "2") (pinfunction "2_2") (pintype "passive"))
      (node (ref "R_ADC_B3") (pin "2") (pinfunction "2_2") (pintype "passive"))
      (node (ref "R_ADC_GND") (pin "2") (pinfunction "2_2") (pintype "passive"))
      (node (ref "R_VSRC3") (pin "1") (pinfunction "1_1") (pintype "passive"))
    )
    (net (code "96") (name "Net-(R_SUM0-Pad1)") (class "Default")
      (node (ref "R_SUM0") (pin "1") (pinfunction "1_1") (pintype "passive"))
      (node (ref "SUM") (pin "2") (pinfunction "2_2") (pintype "passive"))
    )
    (net (code "97") (name "Net-(R_SUM1-Pad1)") (class "Default")
      (node (ref "R_SUM1") (pin "1") (pinfunction "1_1") (pintype "passive"))
      (node (ref "SUM") (pin "4") (pinfunction "4_4") (pintype "passive"))
    )
    (net (code "98") (name "Net-(R_SUM2-Pad1)") (class "Default")
      (node (ref "R_SUM2") (pin "1") (pinfunction "1_1") (pintype "passive"))
      (node (ref "SUM") (pin "6") (pinfunction "6_6") (pintype "passive"))
    )
    (net (code "99") (name "Net-(R_SUM3-Pad1)") (class "Default")
      (node (ref "R_SUM3") (pin "1") (pinfunction "1_1") (pintype "passive"))
      (node (ref "SUM") (pin "8") (pinfunction "8_8") (pintype "passive"))
    )
    (net (code "100") (name "Net-(R_SUM4-Pad1)") (class "Default")
      (node (ref "R_SUM4") (pin "1") (pinfunction "1_1") (pintype "passive"))
      (node (ref "SUM") (pin "10") (pinfunction "10_10") (pintype "passive"))
    )
    (net (code "101") (name "Net-(R_SUM5-Pad1)") (class "Default")
      (node (ref "R_SUM5") (pin "1") (pinfunction "1_1") (pintype "passive"))
      (node (ref "SUM") (pin "12") (pinfunction "12_12") (pintype "passive"))
    )
    (net (code "102") (name "Net-(R_SUM6-Pad1)") (class "Default")
      (node (ref "R_SUM6") (pin "1") (pinfunction "1_1") (pintype "passive"))
      (node (ref "SUM") (pin "14") (pinfunction "14_14") (pintype "passive"))
    )
    (net (code "103") (name "Net-(R_SUM7-Pad1)") (class "Default")
      (node (ref "R_SUM7") (pin "1") (pinfunction "1_1") (pintype "passive"))
      (node (ref "SUM") (pin "16") (pinfunction "16_16") (pintype "passive"))
    )
    (net (code "104") (name "Net-(R_SUM8-Pad1)") (class "Default")
      (node (ref "R_SUM8") (pin "1") (pinfunction "1_1") (pintype "passive"))
      (node (ref "SUM") (pin "18") (pinfunction "18_18") (pintype "passive"))
    )
    (net (code "105") (name "Net-(R_SUM9-Pad1)") (class "Default")
      (node (ref "R_SUM9") (pin "1") (pinfunction "1_1") (pintype "passive"))
      (node (ref "SUM") (pin "20") (pinfunction "20_20") (pintype "passive"))
    )
    (net (code "106") (name "Net-(R_SUM10-Pad1)") (class "Default")
      (node (ref "R_SUM10") (pin "1") (pinfunction "1_1") (pintype "passive"))
      (node (ref "SUM") (pin "22") (pinfunction "22_22") (pintype "passive"))
    )
    (net (code "107") (name "Net-(R_SUM11-Pad1)") (class "Default")
      (node (ref "R_SUM11") (pin "1") (pinfunction "1_1") (pintype "passive"))
      (node (ref "SUM") (pin "24") (pinfunction "24_24") (pintype "passive"))
    )
    (net (code "108") (name "Net-(R_SUM12-Pad1)") (class "Default")
      (node (ref "R_SUM12") (pin "1") (pinfunction "1_1") (pintype "passive"))
      (node (ref "SUM") (pin "26") (pinfunction "26_26") (pintype "passive"))
    )
    (net (code "109") (name "Net-(R_SUM13-Pad1)") (class "Default")
      (node (ref "R_SUM13") (pin "1") (pinfunction "1_1") (pintype "passive"))
      (node (ref "SUM") (pin "28") (pinfunction "28_28") (pintype "passive"))
    )
    (net (code "110") (name "Net-(R_SUM14-Pad1)") (class "Default")
      (node (ref "R_SUM14") (pin "1") (pinfunction "1_1") (pintype "passive"))
      (node (ref "SUM") (pin "30") (pinfunction "30_30") (pintype "passive"))
    )
    (net (code "111") (name "Net-(R_SUM15-Pad1)") (class "Default")
      (node (ref "R_SUM15") (pin "1") (pinfunction "1_1") (pintype "passive"))
      (node (ref "SUM") (pin "32") (pinfunction "32_32") (pintype "passive"))
    )
    (net (code "112") (name "Net-(R_SUMOUT-Pad1)") (class "Default")
      (node (ref "R_SUMOUT") (pin "1") (pinfunction "1_1") (pintype "passive"))
      (node (ref "SUM_OUT0") (pin "1") (pinfunction "1_1") (pintype "passive"))
    )
    (net (code "113") (name "Net-(R_SUMOUT-Pad2)") (class "Default")
      (node (ref "R_SUMOUT") (pin "2") (pinfunction "2_2") (pintype "passive"))
      (node (ref "SUM_SELECT") (pin "3") (pinfunction "3_3") (pintype "passive"))
    )
    (net (code "114") (name "Net-(U0-IN+)") (class "Default")
      (node (ref "R_SUM0") (pin "2") (pinfunction "2_2") (pintype "passive"))
      (node (ref "R_SUM1") (pin "2") (pinfunction "2_2") (pintype "passive"))
      (node (ref "R_SUM10") (pin "2") (pinfunction "2_2") (pintype "passive"))
      (node (ref "R_SUM11") (pin "2") (pinfunction "2_2") (pintype "passive"))
      (node (ref "R_SUM12") (pin "2") (pinfunction "2_2") (pintype "passive"))
      (node (ref "R_SUM13") (pin "2") (pinfunction "2_2") (pintype "passive"))
      (node (ref "R_SUM14") (pin "2") (pinfunction "2_2") (pintype "passive"))
      (node (ref "R_SUM15") (pin "2") (pinfunction "2_2") (pintype "passive"))
      (node (ref "R_SUM2") (pin "2") (pinfunction "2_2") (pintype "passive"))
      (node (ref "R_SUM3") (pin "2") (pinfunction "2_2") (pintype "passive"))
      (node (ref "R_SUM4") (pin "2") (pinfunction "2_2") (pintype "passive"))
      (node (ref "R_SUM5") (pin "2") (pinfunction "2_2") (pintype "passive"))
      (node (ref "R_SUM6") (pin "2") (pinfunction "2_2") (pintype "passive"))
      (node (ref "R_SUM7") (pin "2") (pinfunction "2_2") (pintype "passive"))
      (node (ref "R_SUM8") (pin "2") (pinfunction "2_2") (pintype "passive"))
      (node (ref "R_SUM9") (pin "2") (pinfunction "2_2") (pintype "passive"))
      (node (ref "U0") (pin "3") (pinfunction "IN+_3") (pintype "input"))
    )
    (net (code "115") (name "Net-(U0-IN-)") (class "Default")
      (node (ref "C_f") (pin "1") (pinfunction "1_1") (pintype "passive"))
      (node (ref "R_VSRC1") (pin "1") (pinfunction "1_1") (pintype "passive"))
      (node (ref "R_f") (pin "1") (pinfunction "1_1") (pintype "passive"))
      (node (ref "U0") (pin "4") (pinfunction "IN-_4") (pintype "input"))
    )
    (net (code "116") (name "VCCA") (class "Default")
      (node (ref "C_VPP") (pin "2") (pinfunction "2_2") (pintype "passive"))
      (node (ref "U0") (pin "5") (pinfunction "V+_5") (pintype "power_in"))
    )
  )
)
